# CW308T_CC2538_Micro.net
KiCad netlist of a schematic drawn in Altium Designer
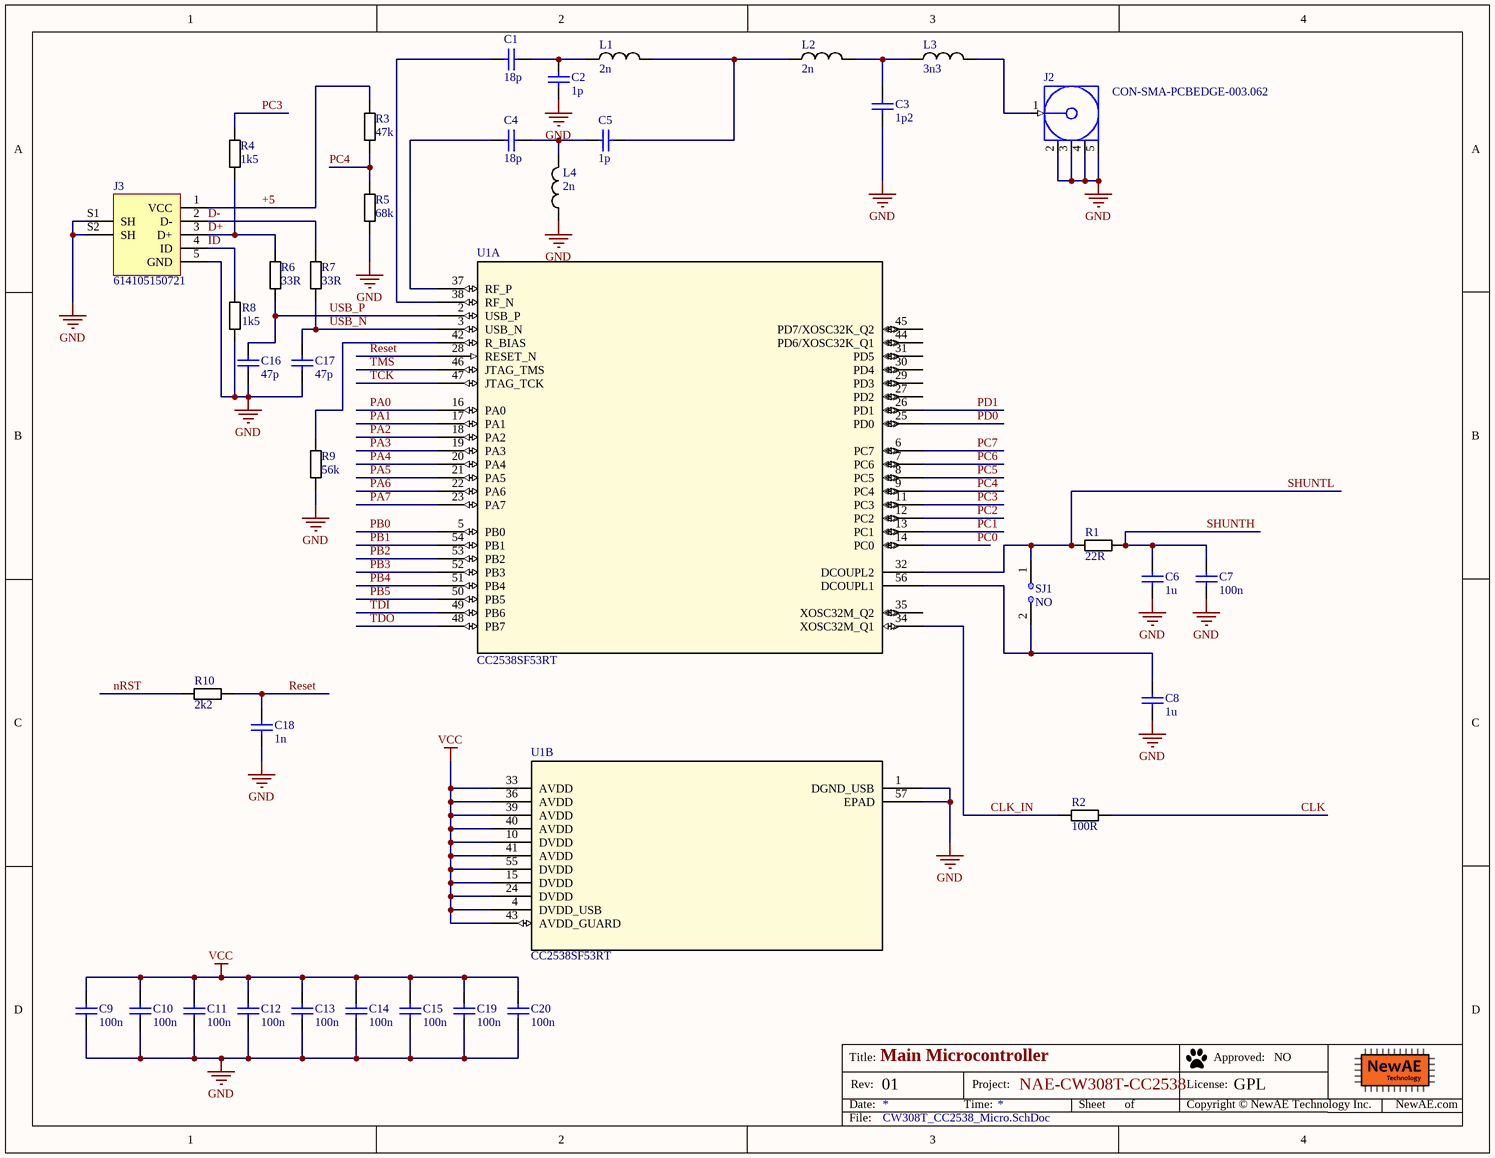
[diagram p0: CW308T_CC2538_Micro.SchDoc]

(export (version "E")
  (design (tool "Eeschema 10.0.6"))
  (components
    (comp (ref "C1")
      (value "18p")
      (footprint "CAPC0402_M")
      (description "18p, 0402")
      (fields (field (name "PART NUMBER") "CCHIP-18p-0402"))
      (libsource (lib "NewAE_AltiumLib") (part "CAP"))
    )
    (comp (ref "C2")
      (value "1p")
      (footprint "CAPC0402_M")
      (description "1p, 0402")
      (fields (field (name "PART NUMBER") "CCHIP-1p-0402"))
      (libsource (lib "NewAE_AltiumLib") (part "CAP"))
    )
    (comp (ref "C3")
      (value "1p2")
      (footprint "CAPC0402_M")
      (description "1p2, 0402")
      (fields (field (name "PART NUMBER") "CCHIP-1p2-0402"))
      (libsource (lib "NewAE_AltiumLib") (part "CAP"))
    )
    (comp (ref "C4")
      (value "18p")
      (footprint "CAPC0402_M")
      (description "18p, 0402")
      (fields (field (name "PART NUMBER") "CCHIP-18p-0402"))
      (libsource (lib "NewAE_AltiumLib") (part "CAP"))
    )
    (comp (ref "C5")
      (value "1p")
      (footprint "CAPC0402_M")
      (description "1p, 0402")
      (fields (field (name "PART NUMBER") "CCHIP-1p-0402"))
      (libsource (lib "NewAE_AltiumLib") (part "CAP"))
    )
    (comp (ref "C6")
      (value "1u")
      (footprint "CAPC0603_M")
      (description "1u, 0603")
      (fields (field (name "PART NUMBER") "CCHIP-1u-0603"))
      (libsource (lib "NewAE_AltiumLib") (part "CAP"))
    )
    (comp (ref "C7")
      (value "100n")
      (footprint "CAPC0603_M")
      (description "100n, 0603")
      (fields (field (name "PART NUMBER") "CCHIP-100n-0603"))
      (libsource (lib "NewAE_AltiumLib") (part "CAP"))
    )
    (comp (ref "C8")
      (value "1u")
      (footprint "CAPC0603_M")
      (description "1u, 0603")
      (fields (field (name "PART NUMBER") "CCHIP-1u-0603"))
      (libsource (lib "NewAE_AltiumLib") (part "CAP"))
    )
    (comp (ref "C9")
      (value "100n")
      (footprint "CAPC0603_M")
      (description "100n, 0603")
      (fields (field (name "PART NUMBER") "CCHIP-100n-0603"))
      (libsource (lib "NewAE_AltiumLib") (part "CAP"))
    )
    (comp (ref "C10")
      (value "100n")
      (footprint "CAPC0603_M")
      (description "100n, 0603")
      (fields (field (name "PART NUMBER") "CCHIP-100n-0603"))
      (libsource (lib "NewAE_AltiumLib") (part "CAP"))
    )
    (comp (ref "C11")
      (value "100n")
      (footprint "CAPC0603_M")
      (description "100n, 0603")
      (fields (field (name "PART NUMBER") "CCHIP-100n-0603"))
      (libsource (lib "NewAE_AltiumLib") (part "CAP"))
    )
    (comp (ref "C12")
      (value "100n")
      (footprint "CAPC0603_M")
      (description "100n, 0603")
      (fields (field (name "PART NUMBER") "CCHIP-100n-0603"))
      (libsource (lib "NewAE_AltiumLib") (part "CAP"))
    )
    (comp (ref "C13")
      (value "100n")
      (footprint "CAPC0603_M")
      (description "100n, 0603")
      (fields (field (name "PART NUMBER") "CCHIP-100n-0603"))
      (libsource (lib "NewAE_AltiumLib") (part "CAP"))
    )
    (comp (ref "C14")
      (value "100n")
      (footprint "CAPC0603_M")
      (description "100n, 0603")
      (fields (field (name "PART NUMBER") "CCHIP-100n-0603"))
      (libsource (lib "NewAE_AltiumLib") (part "CAP"))
    )
    (comp (ref "C15")
      (value "100n")
      (footprint "CAPC0603_M")
      (description "100n, 0603")
      (fields (field (name "PART NUMBER") "CCHIP-100n-0603"))
      (libsource (lib "NewAE_AltiumLib") (part "CAP"))
    )
    (comp (ref "C16")
      (value "47p")
      (footprint "CAPC0603_M")
      (description "47p, 0603")
      (fields (field (name "PART NUMBER") "CCHIP-47p-0603"))
      (libsource (lib "NewAE_AltiumLib") (part "CAP"))
    )
    (comp (ref "C17")
      (value "47p")
      (footprint "CAPC0603_M")
      (description "47p, 0603")
      (fields (field (name "PART NUMBER") "CCHIP-47p-0603"))
      (libsource (lib "NewAE_AltiumLib") (part "CAP"))
    )
    (comp (ref "C18")
      (value "1n")
      (footprint "CAPC0603_M")
      (description "1n, 0603")
      (fields (field (name "PART NUMBER") "CCHIP-1n-0603"))
      (libsource (lib "NewAE_AltiumLib") (part "CAP"))
    )
    (comp (ref "C19")
      (value "100n")
      (footprint "CAPC0603_M")
      (description "100n, 0603")
      (fields (field (name "PART NUMBER") "CCHIP-100n-0603"))
      (libsource (lib "NewAE_AltiumLib") (part "CAP"))
    )
    (comp (ref "C20")
      (value "100n")
      (footprint "CAPC0603_M")
      (description "100n, 0603")
      (fields (field (name "PART NUMBER") "CCHIP-100n-0603"))
      (libsource (lib "NewAE_AltiumLib") (part "CAP"))
    )
    (comp (ref "J2")
      (value "CON-SMA-PCBEDGE-003.062")
      (footprint "CON-SMAM-PCB-EDGE062")
      (description "SMA Female Edge Mount Connector for 0.062\" Thick Board")
      (libsource (lib "NewAE_AltiumLib") (part "CON-SMA-PCBEDGE-003.062"))
    )
    (comp (ref "J3")
      (value "614105150721")
      (footprint "614105150721")
      (description "USB, 5-pin, Upright")
      (libsource (lib "NewAE_AltiumLib") (part "USB_5PIN_2SHIELD"))
    )
    (comp (ref "L1")
      (value "2n")
      (footprint "RESC1005X40N")
      (description "2nF, 0402")
      (fields (field (name "PART NUMBER") "LCHIP-2n-0402"))
      (libsource (lib "NewAE_AltiumLib") (part "IND"))
    )
    (comp (ref "L2")
      (value "2n")
      (footprint "RESC1005X40N")
      (description "2nF, 0402")
      (fields (field (name "PART NUMBER") "LCHIP-2n-0402"))
      (libsource (lib "NewAE_AltiumLib") (part "IND"))
    )
    (comp (ref "L3")
      (value "3n3")
      (footprint "RESC1005X40N")
      (description "3.3nF, 0402")
      (fields (field (name "PART NUMBER") "LCHIP-3n3-0402"))
      (libsource (lib "NewAE_AltiumLib") (part "IND"))
    )
    (comp (ref "L4")
      (value "2n")
      (footprint "RESC1005X40N")
      (description "2nF, 0402")
      (fields (field (name "PART NUMBER") "LCHIP-2n-0402"))
      (libsource (lib "NewAE_AltiumLib") (part "IND"))
    )
    (comp (ref "R1")
      (value "22R")
      (footprint "RESC1608X55N")
      (description "22R res, 0603, 1%, 1/10W")
      (fields (field (name "PART NUMBER") "RCHIP-22R-0603") (field (name "TOLERANCE") "1%"))
      (libsource (lib "") (part "RES-EU_2"))
    )
    (comp (ref "R2")
      (value "100R")
      (footprint "RESC1608X55N")
      (description "100R res, 0603, 1%, 1/10W")
      (fields (field (name "PART NUMBER") "RCHIP-100R-0603") (field (name "TOLERANCE") "1%"))
      (libsource (lib "") (part "RES-EU_2"))
    )
    (comp (ref "R3")
      (value "47k")
      (footprint "RESC1608X55N")
      (description "47k res, 0603, 1%, 1/10W")
      (fields (field (name "PART NUMBER") "RCHIP-47K-0603") (field (name "TOLERANCE") "1%"))
      (libsource (lib "NewAE_AltiumLib") (part "RES-EU"))
    )
    (comp (ref "R4")
      (value "1k5")
      (footprint "RESC1608X55N")
      (description "1k5 res, 0603, 1%, 1/10W")
      (fields (field (name "PART NUMBER") "RCHIP-1K5-0603") (field (name "TOLERANCE") "1%"))
      (libsource (lib "") (part "RES-EU_1"))
    )
    (comp (ref "R5")
      (value "68k")
      (footprint "RESC1608X55N")
      (description "68k res, 0603, 1%, 1/10W")
      (fields (field (name "PART NUMBER") "RCHIP-68K-0603") (field (name "TOLERANCE") "1%"))
      (libsource (lib "NewAE_AltiumLib") (part "RES-EU"))
    )
    (comp (ref "R6")
      (value "33R")
      (footprint "RESC1608X55N")
      (description "33R res, 0603, 1%, 1/10W")
      (fields (field (name "PART NUMBER") "RCHIP-33R-0603") (field (name "TOLERANCE") "1%"))
      (libsource (lib "") (part "RES-EU_1"))
    )
    (comp (ref "R7")
      (value "33R")
      (footprint "RESC1608X55N")
      (description "33R res, 0603, 1%, 1/10W")
      (fields (field (name "PART NUMBER") "RCHIP-33R-0603") (field (name "TOLERANCE") "1%"))
      (libsource (lib "NewAE_AltiumLib") (part "RES-EU"))
    )
    (comp (ref "R8")
      (value "1k5")
      (footprint "RESC1608X55N")
      (description "1k5 res, 0603, 1%, 1/10W")
      (fields (field (name "PART NUMBER") "RCHIP-1K5-0603") (field (name "TOLERANCE") "1%"))
      (libsource (lib "NewAE_AltiumLib") (part "RES-EU"))
    )
    (comp (ref "R9")
      (value "56k")
      (footprint "RESC1608X55N")
      (description "56k res, 0603, 1%, 1/10W")
      (fields (field (name "PART NUMBER") "RCHIP-56K-0603") (field (name "TOLERANCE") "1%"))
      (libsource (lib "") (part "RES-EU_1"))
    )
    (comp (ref "R10")
      (value "2k2")
      (footprint "RESC1608X55N")
      (description "2k2 res, 0603, 1%, 1/10W")
      (fields (field (name "PART NUMBER") "RCHIP-2K2-0603") (field (name "TOLERANCE") "1%"))
      (libsource (lib "") (part "RES-EU_2"))
    )
    (comp (ref "SJ1")
      (value "NO")
      (footprint "SJ_2S_NO")
      (description "Solder Jumper, NO")
      (fields (field (name "PART NUMBER") "SJ_2S_NO"))
      (libsource (lib "NewAE_AltiumLib") (part "SJ_2S_NO"))
    )
    (comp (ref "U1")
      (value "CC2538SF53RT")
      (footprint "QFN50P800X800X100_HS-57M")
      (description "IC RF TXRX+MCU 802.15.4, ARM, ECC/AES/RSA")
      (fields
        (field (name "MANUFACTURER_PART_NUMBER") "cc2538_rtq_56")
        (field (name "PART NUMBER") "CC2538SF53RTQT")
        (field (name "COPYRIGHT") "Copyright (C) 2015 Accelerated Designs. All rights reserved")
      )
      (libsource (lib "NewAE_AltiumLib") (part "CC2538"))
    )
  )
  (nets
    (net (code "1") (name "/+5") (class "Default")
      (node (ref "J3") (pin "1") (pinfunction "VCC_1") (pintype "passive"))
      (node (ref "R3") (pin "1") (pinfunction "1_1") (pintype "passive"))
    )
    (net (code "2") (name "/CLK") (class "Default")
      (node (ref "R2") (pin "2") (pinfunction "2_2") (pintype "passive"))
    )
    (net (code "3") (name "/CLK_IN") (class "Default")
      (node (ref "R2") (pin "1") (pinfunction "1_1") (pintype "passive"))
      (node (ref "U1") (pin "34") (pinfunction "XOSC32M_Q1_34") (pintype "bidirectional"))
    )
    (net (code "4") (name "/D+") (class "Default")
      (node (ref "J3") (pin "3") (pinfunction "D+_3") (pintype "passive"))
      (node (ref "R4") (pin "1") (pinfunction "1_1") (pintype "passive"))
      (node (ref "R6") (pin "2") (pinfunction "2_2") (pintype "passive"))
    )
    (net (code "5") (name "/D-") (class "Default")
      (node (ref "J3") (pin "2") (pinfunction "D-_2") (pintype "passive"))
      (node (ref "R7") (pin "1") (pinfunction "1_1") (pintype "passive"))
    )
    (net (code "6") (name "/ID") (class "Default")
      (node (ref "J3") (pin "4") (pinfunction "ID_4") (pintype "power_in"))
      (node (ref "R8") (pin "1") (pinfunction "1_1") (pintype "passive"))
    )
    (net (code "7") (name "/PA0") (class "Default")
      (node (ref "U1") (pin "16") (pinfunction "PA0_16") (pintype "bidirectional"))
    )
    (net (code "8") (name "/PA1") (class "Default")
      (node (ref "U1") (pin "17") (pinfunction "PA1_17") (pintype "bidirectional"))
    )
    (net (code "9") (name "/PA2") (class "Default")
      (node (ref "U1") (pin "18") (pinfunction "PA2_18") (pintype "bidirectional"))
    )
    (net (code "10") (name "/PA3") (class "Default")
      (node (ref "U1") (pin "19") (pinfunction "PA3_19") (pintype "bidirectional"))
    )
    (net (code "11") (name "/PA4") (class "Default")
      (node (ref "U1") (pin "20") (pinfunction "PA4_20") (pintype "bidirectional"))
    )
    (net (code "12") (name "/PA5") (class "Default")
      (node (ref "U1") (pin "21") (pinfunction "PA5_21") (pintype "bidirectional"))
    )
    (net (code "13") (name "/PA6") (class "Default")
      (node (ref "U1") (pin "22") (pinfunction "PA6_22") (pintype "bidirectional"))
    )
    (net (code "14") (name "/PA7") (class "Default")
      (node (ref "U1") (pin "23") (pinfunction "PA7_23") (pintype "bidirectional"))
    )
    (net (code "15") (name "/PB0") (class "Default")
      (node (ref "U1") (pin "5") (pinfunction "PB0_5") (pintype "bidirectional"))
    )
    (net (code "16") (name "/PB1") (class "Default")
      (node (ref "U1") (pin "54") (pinfunction "PB1_54") (pintype "bidirectional"))
    )
    (net (code "17") (name "/PB2") (class "Default")
      (node (ref "U1") (pin "53") (pinfunction "PB2_53") (pintype "bidirectional"))
    )
    (net (code "18") (name "/PB3") (class "Default")
      (node (ref "U1") (pin "52") (pinfunction "PB3_52") (pintype "bidirectional"))
    )
    (net (code "19") (name "/PB4") (class "Default")
      (node (ref "U1") (pin "51") (pinfunction "PB4_51") (pintype "bidirectional"))
    )
    (net (code "20") (name "/PB5") (class "Default")
      (node (ref "U1") (pin "50") (pinfunction "PB5_50") (pintype "bidirectional"))
    )
    (net (code "21") (name "/PC0") (class "Default")
      (node (ref "U1") (pin "14") (pinfunction "PC0_14") (pintype "bidirectional"))
    )
    (net (code "22") (name "/PC1") (class "Default")
      (node (ref "U1") (pin "13") (pinfunction "PC1_13") (pintype "bidirectional"))
    )
    (net (code "23") (name "/PC2") (class "Default")
      (node (ref "U1") (pin "12") (pinfunction "PC2_12") (pintype "bidirectional"))
    )
    (net (code "24") (name "/PC3") (class "Default")
      (node (ref "R4") (pin "2") (pinfunction "2_2") (pintype "passive"))
      (node (ref "U1") (pin "11") (pinfunction "PC3_11") (pintype "bidirectional"))
    )
    (net (code "25") (name "/PC4") (class "Default")
      (node (ref "R3") (pin "2") (pinfunction "2_2") (pintype "passive"))
      (node (ref "R5") (pin "1") (pinfunction "1_1") (pintype "passive"))
      (node (ref "U1") (pin "9") (pinfunction "PC4_9") (pintype "bidirectional"))
    )
    (net (code "26") (name "/PC5") (class "Default")
      (node (ref "U1") (pin "8") (pinfunction "PC5_8") (pintype "bidirectional"))
    )
    (net (code "27") (name "/PC6") (class "Default")
      (node (ref "U1") (pin "7") (pinfunction "PC6_7") (pintype "bidirectional"))
    )
    (net (code "28") (name "/PC7") (class "Default")
      (node (ref "U1") (pin "6") (pinfunction "PC7_6") (pintype "bidirectional"))
    )
    (net (code "29") (name "/PD0") (class "Default")
      (node (ref "U1") (pin "25") (pinfunction "PD0_25") (pintype "bidirectional"))
    )
    (net (code "30") (name "/PD1") (class "Default")
      (node (ref "U1") (pin "26") (pinfunction "PD1_26") (pintype "bidirectional"))
    )
    (net (code "31") (name "/Reset") (class "Default")
      (node (ref "C18") (pin "1") (pinfunction "1_1") (pintype "passive"))
      (node (ref "R10") (pin "2") (pinfunction "2_2") (pintype "passive"))
      (node (ref "U1") (pin "28") (pinfunction "RESET_N_28") (pintype "input"))
    )
    (net (code "32") (name "/SHUNTH") (class "Default")
      (node (ref "C6") (pin "1") (pinfunction "1_1") (pintype "passive"))
      (node (ref "C7") (pin "1") (pinfunction "1_1") (pintype "passive"))
      (node (ref "R1") (pin "2") (pinfunction "2_2") (pintype "passive"))
    )
    (net (code "33") (name "/SHUNTL") (class "Default")
      (node (ref "R1") (pin "1") (pinfunction "1_1") (pintype "passive"))
      (node (ref "SJ1") (pin "1") (pinfunction "1_1") (pintype "passive"))
      (node (ref "U1") (pin "32") (pinfunction "DCOUPL2_32") (pintype "power_in"))
    )
    (net (code "34") (name "/TCK") (class "Default")
      (node (ref "U1") (pin "47") (pinfunction "JTAG_TCK_47") (pintype "bidirectional"))
    )
    (net (code "35") (name "/TDI") (class "Default")
      (node (ref "U1") (pin "49") (pinfunction "PB6_49") (pintype "bidirectional"))
    )
    (net (code "36") (name "/TDO") (class "Default")
      (node (ref "U1") (pin "48") (pinfunction "PB7_48") (pintype "bidirectional"))
    )
    (net (code "37") (name "/TMS") (class "Default")
      (node (ref "U1") (pin "46") (pinfunction "JTAG_TMS_46") (pintype "bidirectional"))
    )
    (net (code "38") (name "/USB_N") (class "Default")
      (node (ref "C17") (pin "1") (pinfunction "1_1") (pintype "passive"))
      (node (ref "R7") (pin "2") (pinfunction "2_2") (pintype "passive"))
      (node (ref "U1") (pin "3") (pinfunction "USB_N_3") (pintype "bidirectional"))
    )
    (net (code "39") (name "/USB_P") (class "Default")
      (node (ref "C16") (pin "1") (pinfunction "1_1") (pintype "passive"))
      (node (ref "R6") (pin "1") (pinfunction "1_1") (pintype "passive"))
      (node (ref "U1") (pin "2") (pinfunction "USB_P_2") (pintype "bidirectional"))
    )
    (net (code "40") (name "/nRST") (class "Default")
      (node (ref "R10") (pin "1") (pinfunction "1_1") (pintype "passive"))
    )
    (net (code "41") (name "GND") (class "Default")
      (node (ref "C10") (pin "2") (pinfunction "2_2") (pintype "passive"))
      (node (ref "C11") (pin "2") (pinfunction "2_2") (pintype "passive"))
      (node (ref "C12") (pin "2") (pinfunction "2_2") (pintype "passive"))
      (node (ref "C13") (pin "2") (pinfunction "2_2") (pintype "passive"))
      (node (ref "C14") (pin "2") (pinfunction "2_2") (pintype "passive"))
      (node (ref "C15") (pin "2") (pinfunction "2_2") (pintype "passive"))
      (node (ref "C16") (pin "2") (pinfunction "2_2") (pintype "passive"))
      (node (ref "C17") (pin "2") (pinfunction "2_2") (pintype "passive"))
      (node (ref "C18") (pin "2") (pinfunction "2_2") (pintype "passive"))
      (node (ref "C19") (pin "2") (pinfunction "2_2") (pintype "passive"))
      (node (ref "C2") (pin "1") (pinfunction "1_1") (pintype "passive"))
      (node (ref "C20") (pin "2") (pinfunction "2_2") (pintype "passive"))
      (node (ref "C3") (pin "2") (pinfunction "2_2") (pintype "passive"))
      (node (ref "C6") (pin "2") (pinfunction "2_2") (pintype "passive"))
      (node (ref "C7") (pin "2") (pinfunction "2_2") (pintype "passive"))
      (node (ref "C8") (pin "2") (pinfunction "2_2") (pintype "passive"))
      (node (ref "C9") (pin "2") (pinfunction "2_2") (pintype "passive"))
      (node (ref "J2") (pin "2") (pinfunction "GND_2") (pintype "power_in"))
      (node (ref "J2") (pin "3") (pinfunction "GND_3") (pintype "power_in"))
      (node (ref "J2") (pin "4") (pinfunction "GND_4") (pintype "power_in"))
      (node (ref "J2") (pin "5") (pinfunction "GND_5") (pintype "power_in"))
      (node (ref "J3") (pin "5") (pinfunction "GND_5") (pintype "power_in"))
      (node (ref "J3") (pin "S1") (pinfunction "SH_S1") (pintype "passive"))
      (node (ref "J3") (pin "S2") (pinfunction "SH_S2") (pintype "passive"))
      (node (ref "L4") (pin "1") (pinfunction "1_1") (pintype "passive"))
      (node (ref "R5") (pin "2") (pinfunction "2_2") (pintype "passive"))
      (node (ref "R8") (pin "2") (pinfunction "2_2") (pintype "passive"))
      (node (ref "R9") (pin "1") (pinfunction "1_1") (pintype "passive"))
      (node (ref "U1") (pin "1") (pinfunction "DGND_USB_1") (pintype "power_in"))
      (node (ref "U1") (pin "57") (pinfunction "EPAD_57") (pintype "passive"))
    )
    (net (code "42") (name "Net-(C1-Pad2)") (class "Default")
      (node (ref "C1") (pin "2") (pinfunction "2_2") (pintype "passive"))
      (node (ref "C2") (pin "2") (pinfunction "2_2") (pintype "passive"))
      (node (ref "L1") (pin "1") (pinfunction "1_1") (pintype "passive"))
    )
    (net (code "43") (name "Net-(C3-Pad1)") (class "Default")
      (node (ref "C3") (pin "1") (pinfunction "1_1") (pintype "passive"))
      (node (ref "L2") (pin "2") (pinfunction "2_2") (pintype "passive"))
      (node (ref "L3") (pin "1") (pinfunction "1_1") (pintype "passive"))
    )
    (net (code "44") (name "Net-(C4-Pad2)") (class "Default")
      (node (ref "C4") (pin "2") (pinfunction "2_2") (pintype "passive"))
      (node (ref "C5") (pin "1") (pinfunction "1_1") (pintype "passive"))
      (node (ref "L4") (pin "2") (pinfunction "2_2") (pintype "passive"))
    )
    (net (code "45") (name "Net-(C5-Pad2)") (class "Default")
      (node (ref "C5") (pin "2") (pinfunction "2_2") (pintype "passive"))
      (node (ref "L1") (pin "2") (pinfunction "2_2") (pintype "passive"))
      (node (ref "L2") (pin "1") (pinfunction "1_1") (pintype "passive"))
    )
    (net (code "46") (name "Net-(J2-Signal)") (class "Default")
      (node (ref "J2") (pin "1") (pinfunction "Signal_1") (pintype "input"))
      (node (ref "L3") (pin "2") (pinfunction "2_2") (pintype "passive"))
    )
    (net (code "47") (name "Net-(U1A-DCOUPL1)") (class "Default")
      (node (ref "C8") (pin "1") (pinfunction "1_1") (pintype "passive"))
      (node (ref "SJ1") (pin "2") (pinfunction "2_2") (pintype "passive"))
      (node (ref "U1") (pin "56") (pinfunction "DCOUPL1_56") (pintype "power_in"))
    )
    (net (code "48") (name "Net-(U1A-RF_N)") (class "Default")
      (node (ref "C1") (pin "1") (pinfunction "1_1") (pintype "passive"))
      (node (ref "U1") (pin "38") (pinfunction "RF_N_38") (pintype "bidirectional"))
    )
    (net (code "49") (name "Net-(U1A-RF_P)") (class "Default")
      (node (ref "C4") (pin "1") (pinfunction "1_1") (pintype "passive"))
      (node (ref "U1") (pin "37") (pinfunction "RF_P_37") (pintype "bidirectional"))
    )
    (net (code "50") (name "Net-(U1A-R_BIAS)") (class "Default")
      (node (ref "R9") (pin "2") (pinfunction "2_2") (pintype "passive"))
      (node (ref "U1") (pin "42") (pinfunction "R_BIAS_42") (pintype "bidirectional"))
    )
    (net (code "51") (name "VCC") (class "Default")
      (node (ref "C10") (pin "1") (pinfunction "1_1") (pintype "passive"))
      (node (ref "C11") (pin "1") (pinfunction "1_1") (pintype "passive"))
      (node (ref "C12") (pin "1") (pinfunction "1_1") (pintype "passive"))
      (node (ref "C13") (pin "1") (pinfunction "1_1") (pintype "passive"))
      (node (ref "C14") (pin "1") (pinfunction "1_1") (pintype "passive"))
      (node (ref "C15") (pin "1") (pinfunction "1_1") (pintype "passive"))
      (node (ref "C19") (pin "1") (pinfunction "1_1") (pintype "passive"))
      (node (ref "C20") (pin "1") (pinfunction "1_1") (pintype "passive"))
      (node (ref "C9") (pin "1") (pinfunction "1_1") (pintype "passive"))
      (node (ref "U1") (pin "10") (pinfunction "DVDD_10") (pintype "power_in"))
      (node (ref "U1") (pin "15") (pinfunction "DVDD_15") (pintype "power_in"))
      (node (ref "U1") (pin "24") (pinfunction "DVDD_24") (pintype "power_in"))
      (node (ref "U1") (pin "33") (pinfunction "AVDD_33") (pintype "power_in"))
      (node (ref "U1") (pin "36") (pinfunction "AVDD_36") (pintype "power_in"))
      (node (ref "U1") (pin "39") (pinfunction "AVDD_39") (pintype "power_in"))
      (node (ref "U1") (pin "4") (pinfunction "DVDD_USB_4") (pintype "power_in"))
      (node (ref "U1") (pin "40") (pinfunction "AVDD_40") (pintype "power_in"))
      (node (ref "U1") (pin "41") (pinfunction "AVDD_41") (pintype "power_in"))
      (node (ref "U1") (pin "43") (pinfunction "AVDD_GUARD_43") (pintype "bidirectional"))
      (node (ref "U1") (pin "55") (pinfunction "DVDD_55") (pintype "power_in"))
    )
    (net (code "52") (name "unconnected-(U1A-PD2-Pad27)") (class "Default")
      (node (ref "U1") (pin "27") (pinfunction "PD2_27") (pintype "bidirectional"))
    )
    (net (code "53") (name "unconnected-(U1A-PD3-Pad29)") (class "Default")
      (node (ref "U1") (pin "29") (pinfunction "PD3_29") (pintype "bidirectional"))
    )
    (net (code "54") (name "unconnected-(U1A-PD4-Pad30)") (class "Default")
      (node (ref "U1") (pin "30") (pinfunction "PD4_30") (pintype "bidirectional"))
    )
    (net (code "55") (name "unconnected-(U1A-PD5-Pad31)") (class "Default")
      (node (ref "U1") (pin "31") (pinfunction "PD5_31") (pintype "bidirectional"))
    )
    (net (code "56") (name "unconnected-(U1A-PD6{slash}XOSC32K_Q1-Pad44)") (class "Default")
      (node (ref "U1") (pin "44") (pinfunction "PD6/XOSC32K_Q1_44") (pintype "bidirectional"))
    )
    (net (code "57") (name "unconnected-(U1A-PD7{slash}XOSC32K_Q2-Pad45)") (class "Default")
      (node (ref "U1") (pin "45") (pinfunction "PD7/XOSC32K_Q2_45") (pintype "bidirectional"))
    )
    (net (code "58") (name "unconnected-(U1A-XOSC32M_Q2-Pad35)") (class "Default")
      (node (ref "U1") (pin "35") (pinfunction "XOSC32M_Q2_35") (pintype "bidirectional"))
    )
  )
)
